# 04_LED.net
KiCad netlist of a schematic drawn in Altium Designer
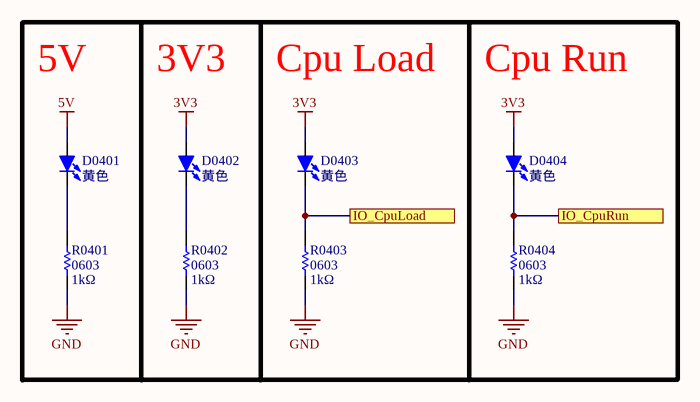
[diagram p0: 04_LED.SchDoc]

(export (version "E")
  (design (tool "Eeschema 10.0.6"))
  (components
    (comp (ref "D0401")
      (value "黄色")
      (footprint "LED 0603Y")
      (description "贴片LED")
      (fields (field (name "版权归属") "源创客"))
      (libsource (lib "LCR") (part "LED-SMD"))
    )
    (comp (ref "D0402")
      (value "黄色")
      (footprint "LED 0603Y")
      (description "贴片LED")
      (fields (field (name "版权归属") "源创客"))
      (libsource (lib "LCR") (part "LED-SMD"))
    )
    (comp (ref "D0403")
      (value "黄色")
      (footprint "LED 0603Y")
      (description "贴片LED")
      (fields (field (name "版权归属") "源创客"))
      (libsource (lib "LCR") (part "LED-SMD"))
    )
    (comp (ref "D0404")
      (value "黄色")
      (footprint "LED 0603Y")
      (description "贴片LED")
      (fields (field (name "版权归属") "源创客"))
      (libsource (lib "LCR") (part "LED-SMD"))
    )
    (comp (ref "R0401")
      (value "RES")
      (footprint "R0402")
      (description "电阻")
      (fields (field (name "SIZE") "0603") (field (name "RES") "1kΩ"))
      (libsource (lib "LCR") (part "RES"))
    )
    (comp (ref "R0402")
      (value "RES")
      (footprint "R0402")
      (description "电阻")
      (fields (field (name "SIZE") "0603") (field (name "RES") "1kΩ"))
      (libsource (lib "LCR") (part "RES"))
    )
    (comp (ref "R0403")
      (value "RES")
      (footprint "R0402")
      (description "电阻")
      (fields (field (name "SIZE") "0603") (field (name "RES") "1kΩ"))
      (libsource (lib "LCR") (part "RES"))
    )
    (comp (ref "R0404")
      (value "RES")
      (footprint "R0402")
      (description "电阻")
      (fields (field (name "SIZE") "0603") (field (name "RES") "1kΩ"))
      (libsource (lib "LCR") (part "RES"))
    )
  )
  (nets
    (net (code "1") (name "/IO_CpuLoad") (class "Default")
      (node (ref "D0403") (pin "K") (pinfunction "K_K") (pintype "passive"))
      (node (ref "R0403") (pin "2") (pinfunction "2_2") (pintype "passive"))
    )
    (net (code "2") (name "/IO_CpuRun") (class "Default")
      (node (ref "D0404") (pin "K") (pinfunction "K_K") (pintype "passive"))
      (node (ref "R0404") (pin "2") (pinfunction "2_2") (pintype "passive"))
    )
    (net (code "3") (name "3V3") (class "Default")
      (node (ref "D0402") (pin "A") (pinfunction "A_A") (pintype "passive"))
      (node (ref "D0403") (pin "A") (pinfunction "A_A") (pintype "passive"))
      (node (ref "D0404") (pin "A") (pinfunction "A_A") (pintype "passive"))
    )
    (net (code "4") (name "5V") (class "Default")
      (node (ref "D0401") (pin "A") (pinfunction "A_A") (pintype "passive"))
    )
    (net (code "5") (name "GND") (class "Default")
      (node (ref "R0401") (pin "1") (pinfunction "1_1") (pintype "passive"))
      (node (ref "R0402") (pin "1") (pinfunction "1_1") (pintype "passive"))
      (node (ref "R0403") (pin "1") (pinfunction "1_1") (pintype "passive"))
      (node (ref "R0404") (pin "1") (pinfunction "1_1") (pintype "passive"))
    )
    (net (code "6") (name "Net-(D0401-PadK)") (class "Default")
      (node (ref "D0401") (pin "K") (pinfunction "K_K") (pintype "passive"))
      (node (ref "R0401") (pin "2") (pinfunction "2_2") (pintype "passive"))
    )
    (net (code "7") (name "Net-(D0402-PadK)") (class "Default")
      (node (ref "D0402") (pin "K") (pinfunction "K_K") (pintype "passive"))
      (node (ref "R0402") (pin "2") (pinfunction "2_2") (pintype "passive"))
    )
  )
)
